# shiftLights.net
KiCad netlist of a schematic drawn in Altium Designer
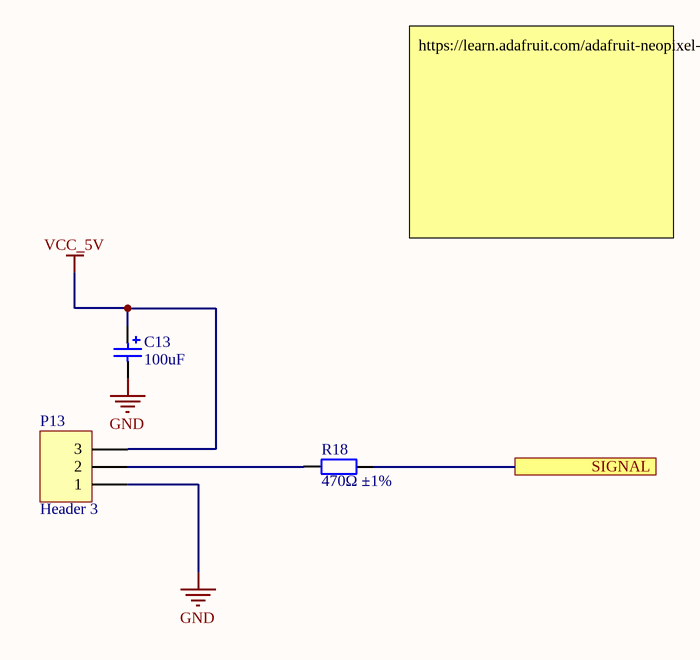
[diagram p0: shiftLights.SchDoc]

(export (version "E")
  (design (tool "Eeschema 10.0.6"))
  (components
    (comp (ref "C13")
      (value "100uF")
      (footprint "CASE-B_3528")
      (description "Tantalum capacitor")
      (fields (field (name "MANUFACTURER") "AVX") (field (name "PARTNUMBER") "TAJB107K006RNJ"))
      (libsource (lib "Cap") (part "3528 100uF (107) 10% 6.3V"))
    )
    (comp (ref "P13")
      (value "Header 3")
      (footprint "HDR1X3")
      (description "Header, 3-Pin")
      (fields (field (name "PUBLISHER") "Altium Limited"))
      (libsource (lib "Miscellaneous Connectors") (part "Header 3"))
    )
    (comp (ref "R18")
      (value "470Ω ±1%")
      (footprint "0603_R")
      (description "Chip resistor")
      (fields (field (name "MANUFACTURER") "Uniroyal Elec") (field (name "PARTNUMBER") "0603WAF4700T5E"))
      (libsource (lib "RES") (part "0603 470R (4700) 1%"))
    )
  )
  (nets
    (net (code "1") (name "/SIGNAL") (class "Default")
      (node (ref "R18") (pin "2") (pinfunction "2_2") (pintype "passive"))
    )
    (net (code "2") (name "GND") (class "Default")
      (node (ref "C13") (pin "2") (pinfunction "2_2") (pintype "passive"))
      (node (ref "P13") (pin "1") (pinfunction "1_1") (pintype "passive"))
    )
    (net (code "3") (name "Net-(P13-Pad2)") (class "Default")
      (node (ref "P13") (pin "2") (pinfunction "2_2") (pintype "passive"))
      (node (ref "R18") (pin "1") (pinfunction "1_1") (pintype "passive"))
    )
    (net (code "4") (name "VCC_5V") (class "Default")
      (node (ref "C13") (pin "1") (pinfunction "1_1") (pintype "passive"))
      (node (ref "P13") (pin "3") (pinfunction "3_3") (pintype "passive"))
    )
  )
)
